# 5v_Spannungsversorgung.net
KiCad netlist of a schematic drawn in EAGLE
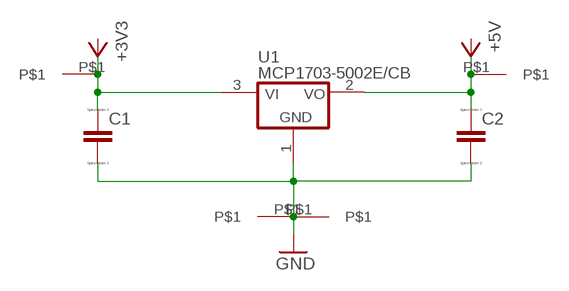
[diagram p0: schematic, sheet 1]

(export (version "E")
  (design (tool "Eeschema 10.0.6"))
  (components
    (comp (ref "C1")
      (value "C-EUC0603K")
      (footprint "eagle-import:C0603K")
      (libsource (lib "eagle-import") (part "C-EUC0603K"))
    )
    (comp (ref "C2")
      (value "C-EUC0603K")
      (footprint "eagle-import:C0603K")
      (libsource (lib "eagle-import") (part "C-EUC0603K"))
    )
    (comp (ref "U$1")
      (value "PAD")
      (footprint "eagle-import:PAD")
      (libsource (lib "eagle-import") (part "PAD"))
    )
    (comp (ref "U$2")
      (value "PAD")
      (footprint "eagle-import:PAD")
      (libsource (lib "eagle-import") (part "PAD"))
    )
    (comp (ref "U$3")
      (value "PAD")
      (footprint "eagle-import:PAD")
      (libsource (lib "eagle-import") (part "PAD"))
    )
    (comp (ref "U$4")
      (value "PAD")
      (footprint "eagle-import:PAD")
      (libsource (lib "eagle-import") (part "PAD"))
    )
    (comp (ref "U1")
      (value "MCP1703-5002E/CB")
      (footprint "eagle-import:SOT23A_MICROCHIP_CB")
      (libsource (lib "eagle-import") (part "MCP170302E/CB-50"))
    )
  )
  (nets
    (net (code "3") (name "GND") (class "Default")
      (node (ref "C1") (pin "2") (pinfunction "2_2") (pintype "passive"))
      (node (ref "C2") (pin "2") (pinfunction "2_2") (pintype "passive"))
      (node (ref "U$2") (pin "P$1") (pinfunction "P$1_P$1") (pintype "bidirectional"))
      (node (ref "U$4") (pin "P$1") (pinfunction "P$1_P$1") (pintype "bidirectional"))
      (node (ref "U1") (pin "1") (pinfunction "GND_1") (pintype "power_in"))
    )
    (net (code "4") (name "Net-(U1-VI)") (class "Default")
      (node (ref "C1") (pin "1") (pinfunction "1_1") (pintype "passive"))
      (node (ref "U$3") (pin "P$1") (pinfunction "P$1_P$1") (pintype "bidirectional"))
      (node (ref "U1") (pin "3") (pinfunction "VI_3") (pintype "power_in"))
    )
    (net (code "5") (name "Net-(U1-VO)") (class "Default")
      (node (ref "C2") (pin "1") (pinfunction "1_1") (pintype "passive"))
      (node (ref "U$1") (pin "P$1") (pinfunction "P$1_P$1") (pintype "bidirectional"))
      (node (ref "U1") (pin "2") (pinfunction "VO_2") (pintype "passive"))
    )
  )
)
